# adns-9500.net
KiCad netlist of a schematic drawn in EAGLE
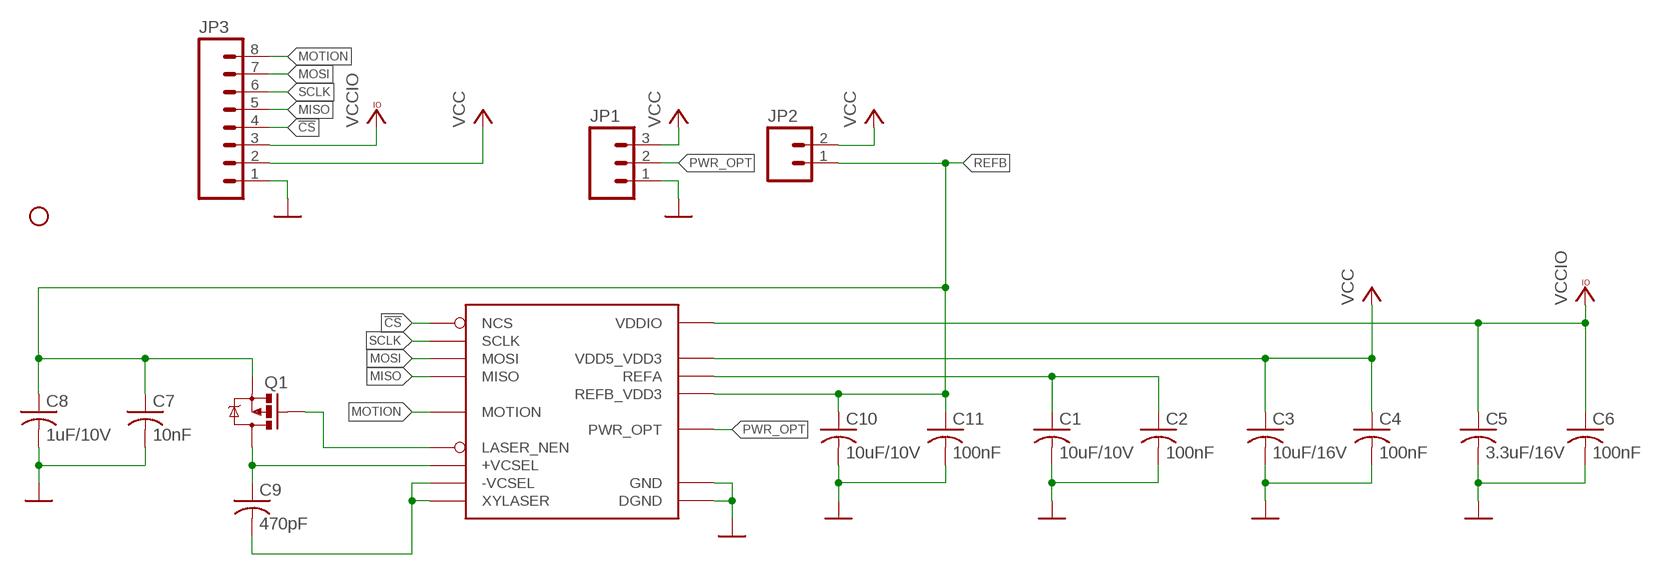
[diagram p0: schematic, sheet 1]

(export (version "E")
  (design (tool "Eeschema 10.0.6"))
  (components
    (comp (ref "C1")
      (value "10uF/10V")
      (footprint "eagle-import:C1206")
      (libsource (lib "eagle-import") (part "C-USC1206"))
    )
    (comp (ref "C2")
      (value "100nF")
      (footprint "eagle-import:C0603")
      (libsource (lib "eagle-import") (part "C-USC0603"))
    )
    (comp (ref "C3")
      (value "10uF/16V")
      (footprint "eagle-import:C1206")
      (libsource (lib "eagle-import") (part "C-USC1206"))
    )
    (comp (ref "C4")
      (value "100nF")
      (footprint "eagle-import:C0603")
      (libsource (lib "eagle-import") (part "C-USC0603"))
    )
    (comp (ref "C5")
      (value "3.3uF/16V")
      (footprint "eagle-import:C1206")
      (libsource (lib "eagle-import") (part "C-USC1206"))
    )
    (comp (ref "C6")
      (value "100nF")
      (footprint "eagle-import:C0603")
      (libsource (lib "eagle-import") (part "C-USC0603"))
    )
    (comp (ref "C7")
      (value "10nF")
      (footprint "eagle-import:C0603")
      (libsource (lib "eagle-import") (part "C-USC0603"))
    )
    (comp (ref "C8")
      (value "1uF/10V")
      (footprint "eagle-import:C0603")
      (libsource (lib "eagle-import") (part "C-USC0603"))
    )
    (comp (ref "C9")
      (value "470pF")
      (footprint "eagle-import:C0603")
      (libsource (lib "eagle-import") (part "C-USC0603"))
    )
    (comp (ref "C10")
      (value "10uF/10V")
      (footprint "eagle-import:C1206")
      (libsource (lib "eagle-import") (part "C-USC1206"))
    )
    (comp (ref "C11")
      (value "100nF")
      (footprint "eagle-import:C0603")
      (libsource (lib "eagle-import") (part "C-USC0603"))
    )
    (comp (ref "JP1")
      (value "M03PTH")
      (footprint "eagle-import:1X03")
      (libsource (lib "eagle-import") (part "M03PTH"))
    )
    (comp (ref "JP2")
      (value "M02PTH")
      (footprint "eagle-import:1X02")
      (libsource (lib "eagle-import") (part "M02PTH"))
    )
    (comp (ref "JP3")
      (value "M081X08")
      (footprint "eagle-import:1X08")
      (libsource (lib "eagle-import") (part "M081X08"))
    )
    (comp (ref "JP4")
      (value "STAND-OFF")
      (footprint "eagle-import:STAND-OFF")
      (libsource (lib "eagle-import") (part "STAND-OFF"))
    )
    (comp (ref "Q1")
      (value "MOSFET-PCHANNELSMD")
      (footprint "eagle-import:SOT23-3")
      (libsource (lib "eagle-import") (part "MOSFET-PCHANNELSMD"))
    )
    (comp (ref "U1")
      (value "AVAGO-ADNS-9500")
      (footprint "eagle-import:AVAGO-ADNS-9500")
      (libsource (lib "eagle-import") (part "AVAGO-ADNS-9500"))
    )
  )
  (nets
    (net (code "1") (name "/~{CS}") (class "Default")
      (node (ref "JP3") (pin "4") (pinfunction "4_4") (pintype "passive"))
      (node (ref "U1") (pin "NCS") (pinfunction "NCS_NCS") (pintype "bidirectional"))
    )
    (net (code "2") (name "GND") (class "Default")
      (node (ref "C1") (pin "2") (pinfunction "2_2") (pintype "passive"))
      (node (ref "C10") (pin "2") (pinfunction "2_2") (pintype "passive"))
      (node (ref "C11") (pin "2") (pinfunction "2_2") (pintype "passive"))
      (node (ref "C2") (pin "2") (pinfunction "2_2") (pintype "passive"))
      (node (ref "C3") (pin "2") (pinfunction "2_2") (pintype "passive"))
      (node (ref "C4") (pin "2") (pinfunction "2_2") (pintype "passive"))
      (node (ref "C5") (pin "2") (pinfunction "2_2") (pintype "passive"))
      (node (ref "C6") (pin "2") (pinfunction "2_2") (pintype "passive"))
      (node (ref "C7") (pin "2") (pinfunction "2_2") (pintype "passive"))
      (node (ref "C8") (pin "2") (pinfunction "2_2") (pintype "passive"))
      (node (ref "JP1") (pin "1") (pinfunction "1_1") (pintype "passive"))
      (node (ref "JP3") (pin "1") (pinfunction "1_1") (pintype "passive"))
      (node (ref "U1") (pin "DGND") (pinfunction "DGND_DGND") (pintype "bidirectional"))
      (node (ref "U1") (pin "GND") (pinfunction "GND_GND") (pintype "bidirectional"))
    )
    (net (code "3") (name "MISO") (class "Default")
      (node (ref "JP3") (pin "5") (pinfunction "5_5") (pintype "passive"))
      (node (ref "U1") (pin "MISO") (pinfunction "MISO_MISO") (pintype "bidirectional"))
    )
    (net (code "4") (name "MOSI") (class "Default")
      (node (ref "JP3") (pin "7") (pinfunction "7_7") (pintype "passive"))
      (node (ref "U1") (pin "MOSI") (pinfunction "MOSI_MOSI") (pintype "bidirectional"))
    )
    (net (code "5") (name "MOTION") (class "Default")
      (node (ref "JP3") (pin "8") (pinfunction "8_8") (pintype "passive"))
      (node (ref "U1") (pin "MOTION") (pinfunction "MOTION_MOTION") (pintype "bidirectional"))
    )
    (net (code "6") (name "Net-(C1-Pad1)") (class "Default")
      (node (ref "C1") (pin "1") (pinfunction "1_1") (pintype "passive"))
      (node (ref "C2") (pin "1") (pinfunction "1_1") (pintype "passive"))
      (node (ref "U1") (pin "REFA") (pinfunction "REFA_REFA") (pintype "bidirectional"))
    )
    (net (code "7") (name "Net-(C9-Pad2)") (class "Default")
      (node (ref "C9") (pin "2") (pinfunction "2_2") (pintype "passive"))
      (node (ref "U1") (pin "-VCSEL") (pinfunction "-VCSEL_-VCSEL") (pintype "bidirectional"))
      (node (ref "U1") (pin "XYLASER") (pinfunction "XYLASER_XYLASER") (pintype "bidirectional"))
    )
    (net (code "8") (name "Net-(Q1-D)") (class "Default")
      (node (ref "C9") (pin "1") (pinfunction "1_1") (pintype "passive"))
      (node (ref "Q1") (pin "3") (pinfunction "D_3") (pintype "passive"))
      (node (ref "U1") (pin "+VCSEL") (pinfunction "+VCSEL_+VCSEL") (pintype "bidirectional"))
    )
    (net (code "9") (name "Net-(Q1-G)") (class "Default")
      (node (ref "Q1") (pin "1") (pinfunction "G_1") (pintype "passive"))
      (node (ref "U1") (pin "LASER_NEN") (pinfunction "LASER_NEN_LASER_NEN") (pintype "bidirectional"))
    )
    (net (code "10") (name "PWR_OPT") (class "Default")
      (node (ref "JP1") (pin "2") (pinfunction "2_2") (pintype "passive"))
      (node (ref "U1") (pin "PWR_OPT") (pinfunction "PWR_OPT_PWR_OPT") (pintype "bidirectional"))
    )
    (net (code "11") (name "REFB") (class "Default")
      (node (ref "C10") (pin "1") (pinfunction "1_1") (pintype "passive"))
      (node (ref "C11") (pin "1") (pinfunction "1_1") (pintype "passive"))
      (node (ref "C7") (pin "1") (pinfunction "1_1") (pintype "passive"))
      (node (ref "C8") (pin "1") (pinfunction "1_1") (pintype "passive"))
      (node (ref "JP2") (pin "1") (pinfunction "1_1") (pintype "passive"))
      (node (ref "Q1") (pin "2") (pinfunction "S_2") (pintype "passive"))
      (node (ref "U1") (pin "REFB_VDD3") (pinfunction "REFB_VDD3_REFB_VDD3") (pintype "bidirectional"))
    )
    (net (code "12") (name "SCLK") (class "Default")
      (node (ref "JP3") (pin "6") (pinfunction "6_6") (pintype "passive"))
      (node (ref "U1") (pin "SCLK") (pinfunction "SCLK_SCLK") (pintype "bidirectional"))
    )
    (net (code "13") (name "VCC") (class "Default")
      (node (ref "C3") (pin "1") (pinfunction "1_1") (pintype "passive"))
      (node (ref "C4") (pin "1") (pinfunction "1_1") (pintype "passive"))
      (node (ref "JP1") (pin "3") (pinfunction "3_3") (pintype "passive"))
      (node (ref "JP2") (pin "2") (pinfunction "2_2") (pintype "passive"))
      (node (ref "JP3") (pin "2") (pinfunction "2_2") (pintype "passive"))
      (node (ref "U1") (pin "VDD5_VDD3") (pinfunction "VDD5_VDD3_VDD5_VDD3") (pintype "bidirectional"))
    )
    (net (code "14") (name "VCCIO") (class "Default")
      (node (ref "C5") (pin "1") (pinfunction "1_1") (pintype "passive"))
      (node (ref "C6") (pin "1") (pinfunction "1_1") (pintype "passive"))
      (node (ref "JP3") (pin "3") (pinfunction "3_3") (pintype "passive"))
      (node (ref "U1") (pin "VDDIO") (pinfunction "VDDIO_VDDIO") (pintype "bidirectional"))
    )
  )
)
